# moe_tuned_lens.net
KiCad netlist of a schematic drawn in EAGLE
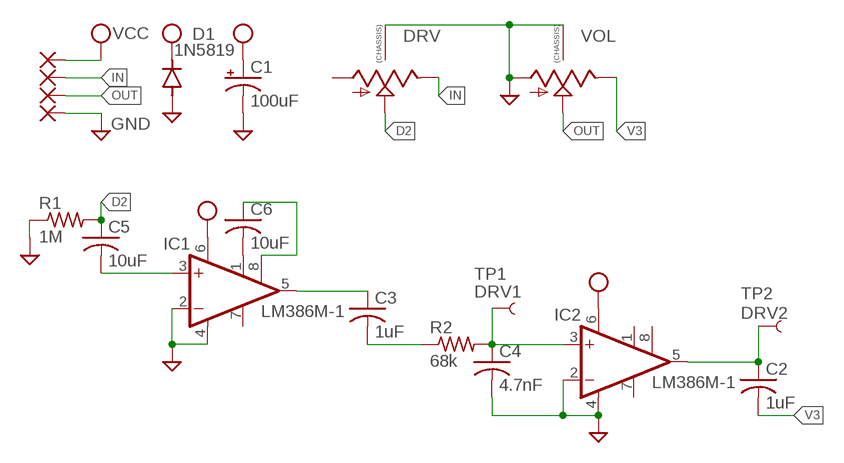
[diagram p0: schematic, sheet 1]

(export (version "E")
  (design (tool "Eeschema 10.0.6"))
  (components
    (comp (ref "C1")
      (value "100uF")
      (footprint "eagle-import:CPOL-RADIAL-2.5MM-6.5MM")
      (libsource (lib "eagle-import") (part "100UF-POLAR-RADIAL-2.5MM-25V-20%"))
    )
    (comp (ref "C2")
      (value "1uF")
      (footprint "eagle-import:C0805")
      (libsource (lib "eagle-import") (part "C-USC0805"))
    )
    (comp (ref "C3")
      (value "1uF")
      (footprint "eagle-import:C0805")
      (libsource (lib "eagle-import") (part "C-USC0805"))
    )
    (comp (ref "C4")
      (value "4.7nF")
      (footprint "eagle-import:C0805")
      (libsource (lib "eagle-import") (part "C-USC0805"))
    )
    (comp (ref "C5")
      (value "10uF")
      (footprint "eagle-import:C1206")
      (libsource (lib "eagle-import") (part "C-USC1206"))
    )
    (comp (ref "C6")
      (value "10uF")
      (footprint "eagle-import:C1206")
      (libsource (lib "eagle-import") (part "C-USC1206"))
    )
    (comp (ref "D1")
      (value "1N5819")
      (footprint "eagle-import:SOD123")
      (libsource (lib "eagle-import") (part "DIODE-SOD123"))
    )
    (comp (ref "DRV")
      (value "9MM_SNAP-IN_POT_CHASSIS")
      (footprint "eagle-import:9MM_SNAP-IN_POT")
      (libsource (lib "eagle-import") (part "9MM_SNAP-IN_POT_CHASSIS"))
    )
    (comp (ref "IC1")
      (value "LM386M-1")
      (footprint "eagle-import:SO08")
      (libsource (lib "eagle-import") (part "LM386?-M1"))
    )
    (comp (ref "IC2")
      (value "LM386M-1")
      (footprint "eagle-import:SO08")
      (libsource (lib "eagle-import") (part "LM386?-M1"))
    )
    (comp (ref "PAD1")
      (value "1,6/0,8")
      (footprint "eagle-import:1,6_0,8")
      (libsource (lib "eagle-import") (part "1,6/0,8"))
    )
    (comp (ref "PAD2")
      (value "1,6/0,8")
      (footprint "eagle-import:1,6_0,8")
      (libsource (lib "eagle-import") (part "1,6/0,8"))
    )
    (comp (ref "PAD3")
      (value "1,6/0,8")
      (footprint "eagle-import:1,6_0,8")
      (libsource (lib "eagle-import") (part "1,6/0,8"))
    )
    (comp (ref "PAD4")
      (value "1,6/0,8")
      (footprint "eagle-import:1,6_0,8")
      (libsource (lib "eagle-import") (part "1,6/0,8"))
    )
    (comp (ref "R1")
      (value "1M")
      (footprint "eagle-import:R0805")
      (libsource (lib "eagle-import") (part "R-US_R0805"))
    )
    (comp (ref "R2")
      (value "68k")
      (footprint "eagle-import:R0805")
      (libsource (lib "eagle-import") (part "R-US_R0805"))
    )
    (comp (ref "TP1")
      (value "DRV1")
      (footprint "eagle-import:PAD.03X.03")
      (libsource (lib "eagle-import") (part "TEST-POINT3"))
    )
    (comp (ref "TP2")
      (value "DRV2")
      (footprint "eagle-import:PAD.03X.03")
      (libsource (lib "eagle-import") (part "TEST-POINT3"))
    )
    (comp (ref "VOL")
      (value "9MM_SNAP-IN_POT_CHASSIS")
      (footprint "eagle-import:9MM_SNAP-IN_POT")
      (libsource (lib "eagle-import") (part "9MM_SNAP-IN_POT_CHASSIS"))
    )
  )
  (nets
    (net (code "1") (name "D2") (class "Default")
      (node (ref "C5") (pin "1") (pinfunction "1_1") (pintype "passive"))
      (node (ref "DRV") (pin "2") (pinfunction "S_2") (pintype "passive"))
      (node (ref "R1") (pin "2") (pinfunction "2_2") (pintype "passive"))
    )
    (net (code "2") (name "GND") (class "Default")
      (node (ref "C1") (pin "2") (pinfunction "-_2") (pintype "passive"))
      (node (ref "C4") (pin "2") (pinfunction "2_2") (pintype "passive"))
      (node (ref "D1") (pin "A") (pinfunction "A_A") (pintype "passive"))
      (node (ref "DRV") (pin "CHASSIS1") (pinfunction "P$1_CHASSIS1") (pintype "passive"))
      (node (ref "DRV") (pin "CHASSIS2") (pinfunction "P$1_CHASSIS2") (pintype "passive"))
      (node (ref "IC1") (pin "2") (pinfunction "-IN_2") (pintype "input"))
      (node (ref "IC1") (pin "4") (pinfunction "GND_4") (pintype "power_in"))
      (node (ref "IC2") (pin "2") (pinfunction "-IN_2") (pintype "input"))
      (node (ref "IC2") (pin "4") (pinfunction "GND_4") (pintype "power_in"))
      (node (ref "PAD4") (pin "1") (pinfunction "P_1") (pintype "passive"))
      (node (ref "R1") (pin "1") (pinfunction "1_1") (pintype "passive"))
      (node (ref "VOL") (pin "1") (pinfunction "A_1") (pintype "passive"))
      (node (ref "VOL") (pin "CHASSIS1") (pinfunction "P$1_CHASSIS1") (pintype "passive"))
      (node (ref "VOL") (pin "CHASSIS2") (pinfunction "P$1_CHASSIS2") (pintype "passive"))
    )
    (net (code "3") (name "IN") (class "Default")
      (node (ref "DRV") (pin "3") (pinfunction "E_3") (pintype "passive"))
      (node (ref "PAD2") (pin "1") (pinfunction "P_1") (pintype "passive"))
    )
    (net (code "4") (name "Net-(C3-Pad2)") (class "Default")
      (node (ref "C3") (pin "2") (pinfunction "2_2") (pintype "passive"))
      (node (ref "R2") (pin "1") (pinfunction "1_1") (pintype "passive"))
    )
    (net (code "5") (name "Net-(C6-Pad1)") (class "Default")
      (node (ref "C6") (pin "1") (pinfunction "1_1") (pintype "passive"))
      (node (ref "IC1") (pin "8") (pinfunction "GAIN_8") (pintype "passive"))
    )
    (net (code "6") (name "Net-(C6-Pad2)") (class "Default")
      (node (ref "C6") (pin "2") (pinfunction "2_2") (pintype "passive"))
      (node (ref "IC1") (pin "1") (pinfunction "GAIN_1") (pintype "passive"))
    )
    (net (code "7") (name "Net-(IC1-+IN)") (class "Default")
      (node (ref "C5") (pin "2") (pinfunction "2_2") (pintype "passive"))
      (node (ref "IC1") (pin "3") (pinfunction "+IN_3") (pintype "input"))
    )
    (net (code "8") (name "Net-(IC1-OUT)") (class "Default")
      (node (ref "C3") (pin "1") (pinfunction "1_1") (pintype "passive"))
      (node (ref "IC1") (pin "5") (pinfunction "OUT_5") (pintype "output"))
    )
    (net (code "9") (name "Net-(IC2-+IN)") (class "Default")
      (node (ref "C4") (pin "1") (pinfunction "1_1") (pintype "passive"))
      (node (ref "IC2") (pin "3") (pinfunction "+IN_3") (pintype "input"))
      (node (ref "R2") (pin "2") (pinfunction "2_2") (pintype "passive"))
      (node (ref "TP1") (pin "P$1") (pinfunction "1_P$1") (pintype "bidirectional"))
    )
    (net (code "10") (name "Net-(IC2-OUT)") (class "Default")
      (node (ref "C2") (pin "1") (pinfunction "1_1") (pintype "passive"))
      (node (ref "IC2") (pin "5") (pinfunction "OUT_5") (pintype "output"))
      (node (ref "TP2") (pin "P$1") (pinfunction "1_P$1") (pintype "bidirectional"))
    )
    (net (code "11") (name "OUT") (class "Default")
      (node (ref "PAD3") (pin "1") (pinfunction "P_1") (pintype "passive"))
      (node (ref "VOL") (pin "2") (pinfunction "S_2") (pintype "passive"))
    )
    (net (code "12") (name "V3") (class "Default")
      (node (ref "C2") (pin "2") (pinfunction "2_2") (pintype "passive"))
      (node (ref "VOL") (pin "3") (pinfunction "E_3") (pintype "passive"))
    )
    (net (code "13") (name "VCC") (class "Default")
      (node (ref "C1") (pin "1") (pinfunction "+_1") (pintype "passive"))
      (node (ref "D1") (pin "C") (pinfunction "C_C") (pintype "passive"))
      (node (ref "IC1") (pin "6") (pinfunction "VS_6") (pintype "power_in"))
      (node (ref "IC2") (pin "6") (pinfunction "VS_6") (pintype "power_in"))
      (node (ref "PAD1") (pin "1") (pinfunction "P_1") (pintype "passive"))
    )
    (net (code "14") (name "unconnected-(DRV-A-Pad1)") (class "Default")
      (node (ref "DRV") (pin "1") (pinfunction "A_1") (pintype "passive"))
    )
    (net (code "15") (name "unconnected-(IC1-BYPASS-Pad7)") (class "Default")
      (node (ref "IC1") (pin "7") (pinfunction "BYPASS_7") (pintype "passive"))
    )
    (net (code "16") (name "unconnected-(IC2-BYPASS-Pad7)") (class "Default")
      (node (ref "IC2") (pin "7") (pinfunction "BYPASS_7") (pintype "passive"))
    )
    (net (code "17") (name "unconnected-(IC2-GAIN-Pad1)") (class "Default")
      (node (ref "IC2") (pin "1") (pinfunction "GAIN_1") (pintype "passive"))
    )
    (net (code "18") (name "unconnected-(IC2-GAIN-Pad8)") (class "Default")
      (node (ref "IC2") (pin "8") (pinfunction "GAIN_8") (pintype "passive"))
    )
  )
)
